# controller.net
KiCad netlist of a schematic drawn in EAGLE
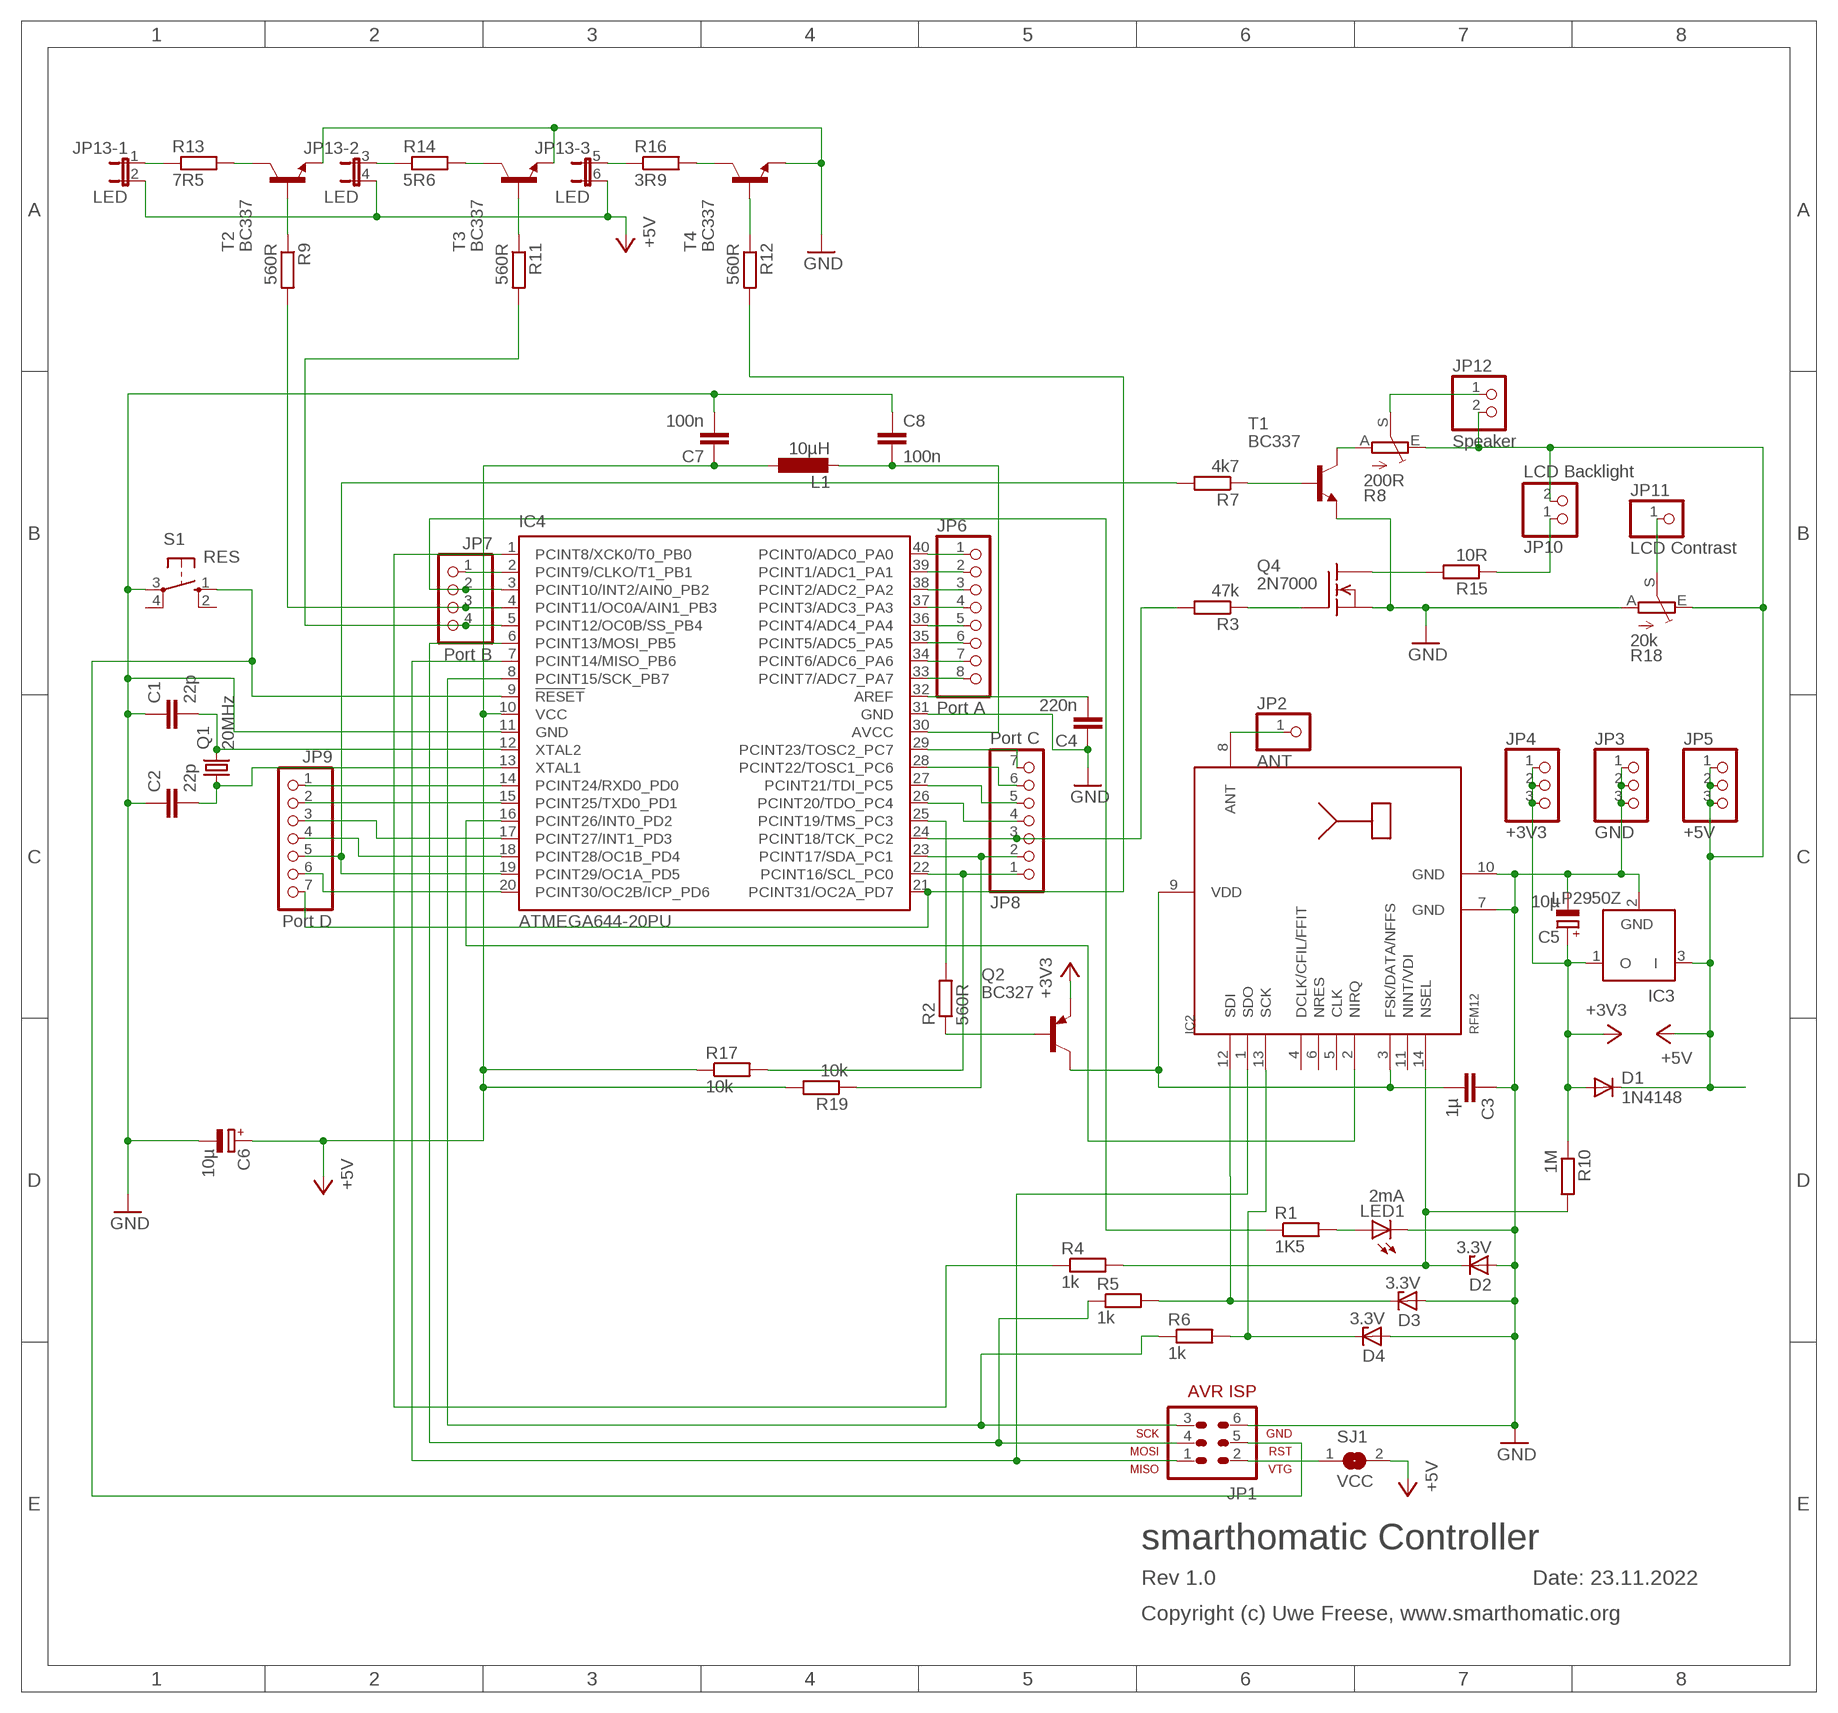
[diagram p0: schematic, sheet 1]

(export (version "E")
  (design (tool "Eeschema 10.0.6"))
  (components
    (comp (ref "C1")
      (value "22p")
      (footprint "eagle-import:C025-024X044")
      (libsource (lib "eagle-import") (part "C-EU025-024X044"))
    )
    (comp (ref "C2")
      (value "22p")
      (footprint "eagle-import:C025-024X044")
      (libsource (lib "eagle-import") (part "C-EU025-024X044"))
    )
    (comp (ref "C3")
      (value "1µ")
      (footprint "eagle-import:C025-030X050")
      (libsource (lib "eagle-import") (part "C-EU025-030X050"))
    )
    (comp (ref "C4")
      (value "220n")
      (footprint "eagle-import:C025-030X050")
      (libsource (lib "eagle-import") (part "C-EU025-030X050"))
    )
    (comp (ref "C5")
      (value "10µ")
      (footprint "eagle-import:E1,8-4")
      (libsource (lib "eagle-import") (part "CPOL-EUE1.8-4"))
    )
    (comp (ref "C6")
      (value "10µ")
      (footprint "eagle-import:E1,8-4")
      (libsource (lib "eagle-import") (part "CPOL-EUE1.8-4"))
    )
    (comp (ref "C7")
      (value "100n")
      (footprint "eagle-import:C050-024X044")
      (libsource (lib "eagle-import") (part "C-EU050-024X044"))
    )
    (comp (ref "C8")
      (value "100n")
      (footprint "eagle-import:C050-024X044")
      (libsource (lib "eagle-import") (part "C-EU050-024X044"))
    )
    (comp (ref "D1")
      (value "1N4148")
      (footprint "eagle-import:DO35-7")
      (libsource (lib "eagle-import") (part "1N4148DO35-7"))
    )
    (comp (ref "D2")
      (value "3.3V")
      (footprint "eagle-import:ZDIO-5")
      (libsource (lib "eagle-import") (part "ZENER-DIODEZD-5"))
    )
    (comp (ref "D3")
      (value "3.3V")
      (footprint "eagle-import:ZDIO-5")
      (libsource (lib "eagle-import") (part "ZENER-DIODEZD-5"))
    )
    (comp (ref "D4")
      (value "3.3V")
      (footprint "eagle-import:ZDIO-5")
      (libsource (lib "eagle-import") (part "ZENER-DIODEZD-5"))
    )
    (comp (ref "IC2")
      (value "RFM12")
      (footprint "eagle-import:RFM")
      (libsource (lib "eagle-import") (part "RFM12"))
    )
    (comp (ref "IC3")
      (value "LP2950Z")
      (footprint "eagle-import:TO92")
      (libsource (lib "eagle-import") (part "LP2950Z"))
    )
    (comp (ref "IC4")
      (value "ATMEGA644-20PU")
      (footprint "eagle-import:DIL40")
      (libsource (lib "eagle-import") (part "ATMEGA644-PU20"))
    )
    (comp (ref "JP1")
      (value "AVR-ISP-6")
      (footprint "eagle-import:AVR-ISP-6")
      (libsource (lib "eagle-import") (part "AVR-ISP-6"))
    )
    (comp (ref "JP2")
      (value "ANT")
      (footprint "eagle-import:1X01")
      (libsource (lib "eagle-import") (part "PINHD-1X1"))
    )
    (comp (ref "JP3")
      (value "GND")
      (footprint "eagle-import:1X03")
      (libsource (lib "eagle-import") (part "PINHD-1X3"))
    )
    (comp (ref "JP4")
      (value "+3V3")
      (footprint "eagle-import:1X03")
      (libsource (lib "eagle-import") (part "PINHD-1X3"))
    )
    (comp (ref "JP5")
      (value "+5V")
      (footprint "eagle-import:1X03")
      (libsource (lib "eagle-import") (part "PINHD-1X3"))
    )
    (comp (ref "JP6")
      (value "Port A")
      (footprint "eagle-import:1X08")
      (libsource (lib "eagle-import") (part "PINHD-1X8"))
    )
    (comp (ref "JP7")
      (value "Port B")
      (footprint "eagle-import:1X04")
      (libsource (lib "eagle-import") (part "PINHD-1X4"))
    )
    (comp (ref "JP8")
      (value "Port C")
      (footprint "eagle-import:1X07")
      (libsource (lib "eagle-import") (part "PINHD-1X7"))
    )
    (comp (ref "JP9")
      (value "Port D")
      (footprint "eagle-import:1X07")
      (libsource (lib "eagle-import") (part "PINHD-1X7"))
    )
    (comp (ref "JP10")
      (value "LCD Backlight")
      (footprint "eagle-import:1X02")
      (libsource (lib "eagle-import") (part "PINHD-1X2"))
    )
    (comp (ref "JP11")
      (value "LCD Contrast")
      (footprint "eagle-import:1X01")
      (libsource (lib "eagle-import") (part "PINHD-1X1"))
    )
    (comp (ref "JP12")
      (value "Speaker")
      (footprint "eagle-import:1X02")
      (libsource (lib "eagle-import") (part "PINHD-1X2"))
    )
    (comp (ref "JP13")
      (value "LED")
      (footprint "eagle-import:JP3Q")
      (libsource (lib "eagle-import") (part "JP3QE"))
    )
    (comp (ref "L1")
      (value "10µH")
      (footprint "eagle-import:0207_10")
      (libsource (lib "eagle-import") (part "L-EU0207/10"))
    )
    (comp (ref "LED1")
      (value "2mA")
      (footprint "eagle-import:LED3MM")
      (libsource (lib "eagle-import") (part "LED3MM"))
    )
    (comp (ref "Q1")
      (value "20MHz")
      (footprint "eagle-import:HC49_S")
      (libsource (lib "eagle-import") (part "CRYSTALHC49S"))
    )
    (comp (ref "Q2")
      (value "BC327")
      (footprint "eagle-import:TO92")
      (libsource (lib "eagle-import") (part "BC327"))
    )
    (comp (ref "Q4")
      (value "2N7000")
      (footprint "eagle-import:TO-92")
      (libsource (lib "eagle-import") (part "TN0602N3"))
    )
    (comp (ref "R1")
      (value "1K5")
      (footprint "eagle-import:0207_7")
      (libsource (lib "eagle-import") (part "R-EU_0207/7"))
    )
    (comp (ref "R2")
      (value "560R")
      (footprint "eagle-import:0207_7")
      (libsource (lib "eagle-import") (part "R-EU_0207/7"))
    )
    (comp (ref "R3")
      (value "47k")
      (footprint "eagle-import:0207_7")
      (libsource (lib "eagle-import") (part "R-EU_0207/7"))
    )
    (comp (ref "R4")
      (value "1k")
      (footprint "eagle-import:0207_7")
      (libsource (lib "eagle-import") (part "R-EU_0207/7"))
    )
    (comp (ref "R5")
      (value "1k")
      (footprint "eagle-import:0207_7")
      (libsource (lib "eagle-import") (part "R-EU_0207/7"))
    )
    (comp (ref "R6")
      (value "1k")
      (footprint "eagle-import:0207_7")
      (libsource (lib "eagle-import") (part "R-EU_0207/7"))
    )
    (comp (ref "R7")
      (value "4k7")
      (footprint "eagle-import:0207_7")
      (libsource (lib "eagle-import") (part "R-EU_0207/7"))
    )
    (comp (ref "R8")
      (value "200R")
      (footprint "eagle-import:CA9H")
      (libsource (lib "eagle-import") (part "TRIM_EU-CA9H"))
    )
    (comp (ref "R9")
      (value "560R")
      (footprint "eagle-import:0207_7")
      (libsource (lib "eagle-import") (part "R-EU_0207/7"))
    )
    (comp (ref "R10")
      (value "1M")
      (footprint "eagle-import:0207_7")
      (libsource (lib "eagle-import") (part "R-EU_0207/7"))
    )
    (comp (ref "R11")
      (value "560R")
      (footprint "eagle-import:0207_7")
      (libsource (lib "eagle-import") (part "R-EU_0207/7"))
    )
    (comp (ref "R12")
      (value "560R")
      (footprint "eagle-import:0207_7")
      (libsource (lib "eagle-import") (part "R-EU_0207/7"))
    )
    (comp (ref "R13")
      (value "7R5")
      (footprint "eagle-import:0207_7")
      (libsource (lib "eagle-import") (part "R-EU_0207/7"))
    )
    (comp (ref "R14")
      (value "5R6")
      (footprint "eagle-import:0207_7")
      (libsource (lib "eagle-import") (part "R-EU_0207/7"))
    )
    (comp (ref "R15")
      (value "10R")
      (footprint "eagle-import:0207_7")
      (libsource (lib "eagle-import") (part "R-EU_0207/7"))
    )
    (comp (ref "R16")
      (value "3R9")
      (footprint "eagle-import:0207_7")
      (libsource (lib "eagle-import") (part "R-EU_0207/7"))
    )
    (comp (ref "R17")
      (value "10k")
      (footprint "eagle-import:0207_7")
      (libsource (lib "eagle-import") (part "R-EU_0207/7"))
    )
    (comp (ref "R18")
      (value "20k")
      (footprint "eagle-import:CA9H")
      (libsource (lib "eagle-import") (part "TRIM_EU-CA9H"))
    )
    (comp (ref "R19")
      (value "10k")
      (footprint "eagle-import:0207_7")
      (libsource (lib "eagle-import") (part "R-EU_0207/7"))
    )
    (comp (ref "S1")
      (value "RES")
      (footprint "eagle-import:B3F-10XX")
      (fields (field (name "MPN") "B3F-1000"))
      (libsource (lib "eagle-import") (part "10-XX"))
    )
    (comp (ref "SJ1")
      (value "VCC")
      (footprint "eagle-import:SJ")
      (libsource (lib "eagle-import") (part "SJ"))
    )
    (comp (ref "T1")
      (value "BC337")
      (footprint "eagle-import:TO92")
      (libsource (lib "eagle-import") (part "BC337"))
    )
    (comp (ref "T2")
      (value "BC337")
      (footprint "eagle-import:TO92")
      (libsource (lib "eagle-import") (part "BC337"))
    )
    (comp (ref "T3")
      (value "BC337")
      (footprint "eagle-import:TO92")
      (libsource (lib "eagle-import") (part "BC337"))
    )
    (comp (ref "T4")
      (value "BC337")
      (footprint "eagle-import:TO92")
      (libsource (lib "eagle-import") (part "BC337"))
    )
  )
  (nets
    (net (code "1") (name "+3V3") (class "Default")
      (node (ref "C5") (pin "+") (pinfunction "+_+") (pintype "passive"))
      (node (ref "D1") (pin "A") (pinfunction "A_A") (pintype "passive"))
      (node (ref "IC3") (pin "1") (pinfunction "O_1") (pintype "input"))
      (node (ref "JP4") (pin "1") (pinfunction "1_1") (pintype "passive"))
      (node (ref "JP4") (pin "2") (pinfunction "2_2") (pintype "passive"))
      (node (ref "JP4") (pin "3") (pinfunction "3_3") (pintype "passive"))
      (node (ref "Q2") (pin "1") (pinfunction "E_1") (pintype "passive"))
      (node (ref "R10") (pin "1") (pinfunction "1_1") (pintype "passive"))
    )
    (net (code "2") (name "+5V") (class "Default")
      (node (ref "C6") (pin "+") (pinfunction "+_+") (pintype "passive"))
      (node (ref "C7") (pin "1") (pinfunction "1_1") (pintype "passive"))
      (node (ref "D1") (pin "C") (pinfunction "C_C") (pintype "passive"))
      (node (ref "IC3") (pin "3") (pinfunction "I_3") (pintype "input"))
      (node (ref "IC4") (pin "10") (pinfunction "VCC_10") (pintype "power_in"))
      (node (ref "JP10") (pin "2") (pinfunction "2_2") (pintype "passive"))
      (node (ref "JP12") (pin "2") (pinfunction "2_2") (pintype "passive"))
      (node (ref "JP13") (pin "2") (pinfunction "2_2") (pintype "passive"))
      (node (ref "JP13") (pin "4") (pinfunction "2_4") (pintype "passive"))
      (node (ref "JP13") (pin "6") (pinfunction "2_6") (pintype "passive"))
      (node (ref "JP5") (pin "1") (pinfunction "1_1") (pintype "passive"))
      (node (ref "JP5") (pin "2") (pinfunction "2_2") (pintype "passive"))
      (node (ref "JP5") (pin "3") (pinfunction "3_3") (pintype "passive"))
      (node (ref "L1") (pin "1") (pinfunction "1_1") (pintype "passive"))
      (node (ref "R17") (pin "1") (pinfunction "1_1") (pintype "passive"))
      (node (ref "R18") (pin "E") (pinfunction "E_E") (pintype "passive"))
      (node (ref "R19") (pin "2") (pinfunction "2_2") (pintype "passive"))
      (node (ref "R8") (pin "E") (pinfunction "E_E") (pintype "passive"))
      (node (ref "SJ1") (pin "2") (pinfunction "2_2") (pintype "passive"))
    )
    (net (code "3") (name "GND") (class "Default")
      (node (ref "C1") (pin "1") (pinfunction "1_1") (pintype "passive"))
      (node (ref "C2") (pin "1") (pinfunction "1_1") (pintype "passive"))
      (node (ref "C3") (pin "1") (pinfunction "1_1") (pintype "passive"))
      (node (ref "C4") (pin "1") (pinfunction "1_1") (pintype "passive"))
      (node (ref "C5") (pin "-") (pinfunction "-_-") (pintype "passive"))
      (node (ref "C6") (pin "-") (pinfunction "-_-") (pintype "passive"))
      (node (ref "C7") (pin "2") (pinfunction "2_2") (pintype "passive"))
      (node (ref "C8") (pin "1") (pinfunction "1_1") (pintype "passive"))
      (node (ref "D2") (pin "A") (pinfunction "A_A") (pintype "passive"))
      (node (ref "D3") (pin "A") (pinfunction "A_A") (pintype "passive"))
      (node (ref "D4") (pin "A") (pinfunction "A_A") (pintype "passive"))
      (node (ref "IC2") (pin "10") (pinfunction "GND_10") (pintype "power_in"))
      (node (ref "IC2") (pin "7") (pinfunction "GND_7") (pintype "power_in"))
      (node (ref "IC3") (pin "2") (pinfunction "GND_2") (pintype "power_in"))
      (node (ref "IC4") (pin "11") (pinfunction "GND_11") (pintype "power_in"))
      (node (ref "IC4") (pin "31") (pinfunction "GND_31") (pintype "power_in"))
      (node (ref "JP1") (pin "6") (pinfunction "6_6") (pintype "passive"))
      (node (ref "JP3") (pin "1") (pinfunction "1_1") (pintype "passive"))
      (node (ref "JP3") (pin "2") (pinfunction "2_2") (pintype "passive"))
      (node (ref "JP3") (pin "3") (pinfunction "3_3") (pintype "passive"))
      (node (ref "LED1") (pin "K") (pinfunction "C_K") (pintype "passive"))
      (node (ref "Q4") (pin "1") (pinfunction "S_1") (pintype "passive"))
      (node (ref "R18") (pin "A") (pinfunction "A_A") (pintype "passive"))
      (node (ref "S1") (pin "3") (pinfunction "P_3") (pintype "passive"))
      (node (ref "T1") (pin "1") (pinfunction "E_1") (pintype "passive"))
      (node (ref "T2") (pin "1") (pinfunction "E_1") (pintype "passive"))
      (node (ref "T3") (pin "1") (pinfunction "E_1") (pintype "passive"))
      (node (ref "T4") (pin "1") (pinfunction "E_1") (pintype "passive"))
    )
    (net (code "4") (name "Net-(IC2-ANT)") (class "Default")
      (node (ref "IC2") (pin "8") (pinfunction "ANT_8") (pintype "output"))
      (node (ref "JP2") (pin "1") (pinfunction "1_1") (pintype "passive"))
    )
    (net (code "5") (name "Net-(IC2-FSK{slash}DATA{slash}NFFS)") (class "Default")
      (node (ref "C3") (pin "2") (pinfunction "2_2") (pintype "passive"))
      (node (ref "IC2") (pin "3") (pinfunction "FSK/DATA/NFFS_3") (pintype "bidirectional"))
      (node (ref "IC2") (pin "9") (pinfunction "VDD_9") (pintype "power_in"))
      (node (ref "Q2") (pin "3") (pinfunction "C_3") (pintype "passive"))
    )
    (net (code "6") (name "Net-(IC2-NIRQ)") (class "Default")
      (node (ref "IC2") (pin "2") (pinfunction "NIRQ_2") (pintype "bidirectional"))
      (node (ref "IC4") (pin "16") (pinfunction "PCINT26/INT0_PD2_16") (pintype "bidirectional"))
    )
    (net (code "7") (name "Net-(IC2-NSEL)") (class "Default")
      (node (ref "D2") (pin "C") (pinfunction "C_C") (pintype "passive"))
      (node (ref "IC2") (pin "14") (pinfunction "NSEL_14") (pintype "bidirectional"))
      (node (ref "R10") (pin "2") (pinfunction "2_2") (pintype "passive"))
      (node (ref "R4") (pin "2") (pinfunction "2_2") (pintype "passive"))
    )
    (net (code "8") (name "Net-(IC2-SCK)") (class "Default")
      (node (ref "D4") (pin "C") (pinfunction "C_C") (pintype "passive"))
      (node (ref "IC2") (pin "13") (pinfunction "SCK_13") (pintype "bidirectional"))
      (node (ref "R6") (pin "2") (pinfunction "2_2") (pintype "passive"))
    )
    (net (code "9") (name "Net-(IC2-SDI)") (class "Default")
      (node (ref "D3") (pin "C") (pinfunction "C_C") (pintype "passive"))
      (node (ref "IC2") (pin "12") (pinfunction "SDI_12") (pintype "bidirectional"))
      (node (ref "R5") (pin "2") (pinfunction "2_2") (pintype "passive"))
    )
    (net (code "10") (name "Net-(IC2-SDO)") (class "Default")
      (node (ref "IC2") (pin "1") (pinfunction "SDO_1") (pintype "bidirectional"))
      (node (ref "IC4") (pin "7") (pinfunction "PCINT14/MISO_PB6_7") (pintype "bidirectional"))
      (node (ref "JP1") (pin "1") (pinfunction "1_1") (pintype "passive"))
    )
    (net (code "11") (name "Net-(IC4-AREF)") (class "Default")
      (node (ref "C4") (pin "2") (pinfunction "2_2") (pintype "passive"))
      (node (ref "IC4") (pin "32") (pinfunction "AREF_32") (pintype "passive"))
    )
    (net (code "12") (name "Net-(IC4-AVCC)") (class "Default")
      (node (ref "C8") (pin "2") (pinfunction "2_2") (pintype "passive"))
      (node (ref "IC4") (pin "30") (pinfunction "AVCC_30") (pintype "power_in"))
      (node (ref "L1") (pin "2") (pinfunction "2_2") (pintype "passive"))
    )
    (net (code "13") (name "Net-(IC4-PCINT0{slash}ADC0_PA0)") (class "Default")
      (node (ref "IC4") (pin "40") (pinfunction "PCINT0/ADC0_PA0_40") (pintype "bidirectional"))
      (node (ref "JP6") (pin "1") (pinfunction "1_1") (pintype "passive"))
    )
    (net (code "14") (name "Net-(IC4-PCINT1{slash}ADC1_PA1)") (class "Default")
      (node (ref "IC4") (pin "39") (pinfunction "PCINT1/ADC1_PA1_39") (pintype "bidirectional"))
      (node (ref "JP6") (pin "2") (pinfunction "2_2") (pintype "passive"))
    )
    (net (code "15") (name "Net-(IC4-PCINT2{slash}ADC2_PA2)") (class "Default")
      (node (ref "IC4") (pin "38") (pinfunction "PCINT2/ADC2_PA2_38") (pintype "bidirectional"))
      (node (ref "JP6") (pin "3") (pinfunction "3_3") (pintype "passive"))
    )
    (net (code "16") (name "Net-(IC4-PCINT3{slash}ADC3_PA3)") (class "Default")
      (node (ref "IC4") (pin "37") (pinfunction "PCINT3/ADC3_PA3_37") (pintype "bidirectional"))
      (node (ref "JP6") (pin "4") (pinfunction "4_4") (pintype "passive"))
    )
    (net (code "17") (name "Net-(IC4-PCINT4{slash}ADC4_PA4)") (class "Default")
      (node (ref "IC4") (pin "36") (pinfunction "PCINT4/ADC4_PA4_36") (pintype "bidirectional"))
      (node (ref "JP6") (pin "5") (pinfunction "5_5") (pintype "passive"))
    )
    (net (code "18") (name "Net-(IC4-PCINT5{slash}ADC5_PA5)") (class "Default")
      (node (ref "IC4") (pin "35") (pinfunction "PCINT5/ADC5_PA5_35") (pintype "bidirectional"))
      (node (ref "JP6") (pin "6") (pinfunction "6_6") (pintype "passive"))
    )
    (net (code "19") (name "Net-(IC4-PCINT6{slash}ADC6_PA6)") (class "Default")
      (node (ref "IC4") (pin "34") (pinfunction "PCINT6/ADC6_PA6_34") (pintype "bidirectional"))
      (node (ref "JP6") (pin "7") (pinfunction "7_7") (pintype "passive"))
    )
    (net (code "20") (name "Net-(IC4-PCINT7{slash}ADC7_PA7)") (class "Default")
      (node (ref "IC4") (pin "33") (pinfunction "PCINT7/ADC7_PA7_33") (pintype "bidirectional"))
      (node (ref "JP6") (pin "8") (pinfunction "8_8") (pintype "passive"))
    )
    (net (code "21") (name "Net-(IC4-PCINT8{slash}XCK0{slash}T0_PB0)") (class "Default")
      (node (ref "IC4") (pin "1") (pinfunction "PCINT8/XCK0/T0_PB0_1") (pintype "bidirectional"))
      (node (ref "R4") (pin "1") (pinfunction "1_1") (pintype "passive"))
    )
    (net (code "22") (name "Net-(IC4-PCINT9{slash}CLKO{slash}T1_PB1)") (class "Default")
      (node (ref "IC4") (pin "2") (pinfunction "PCINT9/CLKO/T1_PB1_2") (pintype "bidirectional"))
      (node (ref "JP7") (pin "1") (pinfunction "1_1") (pintype "passive"))
    )
    (net (code "23") (name "Net-(IC4-PCINT10{slash}INT2{slash}AIN0_PB2)") (class "Default")
      (node (ref "IC4") (pin "3") (pinfunction "PCINT10/INT2/AIN0_PB2_3") (pintype "bidirectional"))
      (node (ref "JP7") (pin "2") (pinfunction "2_2") (pintype "passive"))
      (node (ref "R1") (pin "1") (pinfunction "1_1") (pintype "passive"))
    )
    (net (code "24") (name "Net-(IC4-PCINT11{slash}OC0A{slash}AIN1_PB3)") (class "Default")
      (node (ref "IC4") (pin "4") (pinfunction "PCINT11/OC0A/AIN1_PB3_4") (pintype "bidirectional"))
      (node (ref "JP7") (pin "3") (pinfunction "3_3") (pintype "passive"))
      (node (ref "R9") (pin "2") (pinfunction "2_2") (pintype "passive"))
    )
    (net (code "25") (name "Net-(IC4-PCINT12{slash}OC0B{slash}SS_PB4)") (class "Default")
      (node (ref "IC4") (pin "5") (pinfunction "PCINT12/OC0B/SS_PB4_5") (pintype "bidirectional"))
      (node (ref "JP7") (pin "4") (pinfunction "4_4") (pintype "passive"))
      (node (ref "R11") (pin "2") (pinfunction "2_2") (pintype "passive"))
    )
    (net (code "26") (name "Net-(IC4-PCINT13{slash}MOSI_PB5)") (class "Default")
      (node (ref "IC4") (pin "6") (pinfunction "PCINT13/MOSI_PB5_6") (pintype "bidirectional"))
      (node (ref "JP1") (pin "4") (pinfunction "4_4") (pintype "passive"))
      (node (ref "R5") (pin "1") (pinfunction "1_1") (pintype "passive"))
    )
    (net (code "27") (name "Net-(IC4-PCINT15{slash}SCK_PB7)") (class "Default")
      (node (ref "IC4") (pin "8") (pinfunction "PCINT15/SCK_PB7_8") (pintype "bidirectional"))
      (node (ref "JP1") (pin "3") (pinfunction "3_3") (pintype "passive"))
      (node (ref "R6") (pin "1") (pinfunction "1_1") (pintype "passive"))
    )
    (net (code "28") (name "Net-(IC4-PCINT16{slash}SCL_PC0)") (class "Default")
      (node (ref "IC4") (pin "22") (pinfunction "PCINT16/SCL_PC0_22") (pintype "bidirectional"))
      (node (ref "JP8") (pin "1") (pinfunction "1_1") (pintype "passive"))
      (node (ref "R17") (pin "2") (pinfunction "2_2") (pintype "passive"))
    )
    (net (code "29") (name "Net-(IC4-PCINT17{slash}SDA_PC1)") (class "Default")
      (node (ref "IC4") (pin "23") (pinfunction "PCINT17/SDA_PC1_23") (pintype "bidirectional"))
      (node (ref "JP8") (pin "2") (pinfunction "2_2") (pintype "passive"))
      (node (ref "R19") (pin "1") (pinfunction "1_1") (pintype "passive"))
    )
    (net (code "30") (name "Net-(IC4-PCINT18{slash}TCK_PC2)") (class "Default")
      (node (ref "IC4") (pin "24") (pinfunction "PCINT18/TCK_PC2_24") (pintype "bidirectional"))
      (node (ref "JP8") (pin "3") (pinfunction "3_3") (pintype "passive"))
      (node (ref "R3") (pin "2") (pinfunction "2_2") (pintype "passive"))
    )
    (net (code "31") (name "Net-(IC4-PCINT19{slash}TMS_PC3)") (class "Default")
      (node (ref "IC4") (pin "25") (pinfunction "PCINT19/TMS_PC3_25") (pintype "bidirectional"))
      (node (ref "R2") (pin "2") (pinfunction "2_2") (pintype "passive"))
    )
    (net (code "32") (name "Net-(IC4-PCINT20{slash}TDO_PC4)") (class "Default")
      (node (ref "IC4") (pin "26") (pinfunction "PCINT20/TDO_PC4_26") (pintype "bidirectional"))
      (node (ref "JP8") (pin "4") (pinfunction "4_4") (pintype "passive"))
    )
    (net (code "33") (name "Net-(IC4-PCINT21{slash}TDI_PC5)") (class "Default")
      (node (ref "IC4") (pin "27") (pinfunction "PCINT21/TDI_PC5_27") (pintype "bidirectional"))
      (node (ref "JP8") (pin "5") (pinfunction "5_5") (pintype "passive"))
    )
    (net (code "34") (name "Net-(IC4-PCINT22{slash}TOSC1_PC6)") (class "Default")
      (node (ref "IC4") (pin "28") (pinfunction "PCINT22/TOSC1_PC6_28") (pintype "bidirectional"))
      (node (ref "JP8") (pin "6") (pinfunction "6_6") (pintype "passive"))
    )
    (net (code "35") (name "Net-(IC4-PCINT23{slash}TOSC2_PC7)") (class "Default")
      (node (ref "IC4") (pin "29") (pinfunction "PCINT23/TOSC2_PC7_29") (pintype "bidirectional"))
      (node (ref "JP8") (pin "7") (pinfunction "7_7") (pintype "passive"))
    )
    (net (code "36") (name "Net-(IC4-PCINT24{slash}RXD0_PD0)") (class "Default")
      (node (ref "IC4") (pin "14") (pinfunction "PCINT24/RXD0_PD0_14") (pintype "bidirectional"))
      (node (ref "JP9") (pin "1") (pinfunction "1_1") (pintype "passive"))
    )
    (net (code "37") (name "Net-(IC4-PCINT25{slash}TXD0_PD1)") (class "Default")
      (node (ref "IC4") (pin "15") (pinfunction "PCINT25/TXD0_PD1_15") (pintype "bidirectional"))
      (node (ref "JP9") (pin "2") (pinfunction "2_2") (pintype "passive"))
    )
    (net (code "38") (name "Net-(IC4-PCINT27{slash}INT1_PD3)") (class "Default")
      (node (ref "IC4") (pin "17") (pinfunction "PCINT27/INT1_PD3_17") (pintype "bidirectional"))
      (node (ref "JP9") (pin "3") (pinfunction "3_3") (pintype "passive"))
    )
    (net (code "39") (name "Net-(IC4-PCINT28{slash}OC1B_PD4)") (class "Default")
      (node (ref "IC4") (pin "18") (pinfunction "PCINT28/OC1B_PD4_18") (pintype "bidirectional"))
      (node (ref "JP9") (pin "4") (pinfunction "4_4") (pintype "passive"))
    )
    (net (code "40") (name "Net-(IC4-PCINT29{slash}OC1A_PD5)") (class "Default")
      (node (ref "IC4") (pin "19") (pinfunction "PCINT29/OC1A_PD5_19") (pintype "bidirectional"))
      (node (ref "JP9") (pin "5") (pinfunction "5_5") (pintype "passive"))
      (node (ref "R7") (pin "2") (pinfunction "2_2") (pintype "passive"))
    )
    (net (code "41") (name "Net-(IC4-PCINT30{slash}OC2B{slash}ICP_PD6)") (class "Default")
      (node (ref "IC4") (pin "20") (pinfunction "PCINT30/OC2B/ICP_PD6_20") (pintype "bidirectional"))
      (node (ref "JP9") (pin "6") (pinfunction "6_6") (pintype "passive"))
    )
    (net (code "42") (name "Net-(IC4-PCINT31{slash}OC2A_PD7)") (class "Default")
      (node (ref "IC4") (pin "21") (pinfunction "PCINT31/OC2A_PD7_21") (pintype "bidirectional"))
      (node (ref "JP9") (pin "7") (pinfunction "7_7") (pintype "passive"))
      (node (ref "R12") (pin "2") (pinfunction "2_2") (pintype "passive"))
    )
    (net (code "43") (name "Net-(IC4-XTAL1)") (class "Default")
      (node (ref "C2") (pin "2") (pinfunction "2_2") (pintype "passive"))
      (node (ref "IC4") (pin "13") (pinfunction "XTAL1_13") (pintype "input"))
      (node (ref "Q1") (pin "1") (pinfunction "1_1") (pintype "passive"))
    )
    (net (code "44") (name "Net-(IC4-XTAL2)") (class "Default")
      (node (ref "C1") (pin "2") (pinfunction "2_2") (pintype "passive"))
      (node (ref "IC4") (pin "12") (pinfunction "XTAL2_12") (pintype "output"))
      (node (ref "Q1") (pin "2") (pinfunction "2_2") (pintype "passive"))
    )
    (net (code "45") (name "Net-(IC4-~{RESET})") (class "Default")
      (node (ref "IC4") (pin "9") (pinfunction "~{RESET}_9") (pintype "input"))
      (node (ref "JP1") (pin "5") (pinfunction "5_5") (pintype "passive"))
      (node (ref "S1") (pin "1") (pinfunction "S_1") (pintype "passive"))
    )
    (net (code "46") (name "Net-(JP1-Pad2)") (class "Default")
      (node (ref "JP1") (pin "2") (pinfunction "2_2") (pintype "passive"))
      (node (ref "SJ1") (pin "1") (pinfunction "1_1") (pintype "passive"))
    )
    (net (code "47") (name "Net-(JP10-Pad1)") (class "Default")
      (node (ref "JP10") (pin "1") (pinfunction "1_1") (pintype "passive"))
      (node (ref "R15") (pin "1") (pinfunction "1_1") (pintype "passive"))
    )
    (net (code "48") (name "Net-(JP11-Pad1)") (class "Default")
      (node (ref "JP11") (pin "1") (pinfunction "1_1") (pintype "passive"))
      (node (ref "R18") (pin "S") (pinfunction "S_S") (pintype "passive"))
    )
    (net (code "49") (name "Net-(JP12-Pad1)") (class "Default")
      (node (ref "JP12") (pin "1") (pinfunction "1_1") (pintype "passive"))
      (node (ref "R8") (pin "S") (pinfunction "S_S") (pintype "passive"))
    )
    (net (code "50") (name "Net-(JP13-Pad1)") (class "Default")
      (node (ref "JP13") (pin "1") (pinfunction "1_1") (pintype "passive"))
      (node (ref "R13") (pin "1") (pinfunction "1_1") (pintype "passive"))
    )
    (net (code "51") (name "Net-(JP13B-1)") (class "Default")
      (node (ref "JP13") (pin "3") (pinfunction "1_3") (pintype "passive"))
      (node (ref "R14") (pin "1") (pinfunction "1_1") (pintype "passive"))
    )
    (net (code "52") (name "Net-(JP13C-1)") (class "Default")
      (node (ref "JP13") (pin "5") (pinfunction "1_5") (pintype "passive"))
      (node (ref "R16") (pin "1") (pinfunction "1_1") (pintype "passive"))
    )
    (net (code "53") (name "Net-(LED1-PadA)") (class "Default")
      (node (ref "LED1") (pin "A") (pinfunction "A_A") (pintype "passive"))
      (node (ref "R1") (pin "2") (pinfunction "2_2") (pintype "passive"))
    )
    (net (code "54") (name "Net-(Q2-B)") (class "Default")
      (node (ref "Q2") (pin "2") (pinfunction "B_2") (pintype "passive"))
      (node (ref "R2") (pin "1") (pinfunction "1_1") (pintype "passive"))
    )
    (net (code "55") (name "Net-(Q4-D)") (class "Default")
      (node (ref "Q4") (pin "3") (pinfunction "D_3") (pintype "passive"))
      (node (ref "R15") (pin "2") (pinfunction "2_2") (pintype "passive"))
    )
    (net (code "56") (name "Net-(Q4-G)") (class "Default")
      (node (ref "Q4") (pin "2") (pinfunction "G_2") (pintype "passive"))
      (node (ref "R3") (pin "1") (pinfunction "1_1") (pintype "passive"))
    )
    (net (code "57") (name "Net-(T1-B)") (class "Default")
      (node (ref "R7") (pin "1") (pinfunction "1_1") (pintype "passive"))
      (node (ref "T1") (pin "2") (pinfunction "B_2") (pintype "passive"))
    )
    (net (code "58") (name "Net-(T1-C)") (class "Default")
      (node (ref "R8") (pin "A") (pinfunction "A_A") (pintype "passive"))
      (node (ref "T1") (pin "3") (pinfunction "C_3") (pintype "passive"))
    )
    (net (code "59") (name "Net-(T2-B)") (class "Default")
      (node (ref "R9") (pin "1") (pinfunction "1_1") (pintype "passive"))
      (node (ref "T2") (pin "2") (pinfunction "B_2") (pintype "passive"))
    )
    (net (code "60") (name "Net-(T2-C)") (class "Default")
      (node (ref "R13") (pin "2") (pinfunction "2_2") (pintype "passive"))
      (node (ref "T2") (pin "3") (pinfunction "C_3") (pintype "passive"))
    )
    (net (code "61") (name "Net-(T3-B)") (class "Default")
      (node (ref "R11") (pin "1") (pinfunction "1_1") (pintype "passive"))
      (node (ref "T3") (pin "2") (pinfunction "B_2") (pintype "passive"))
    )
    (net (code "62") (name "Net-(T3-C)") (class "Default")
      (node (ref "R14") (pin "2") (pinfunction "2_2") (pintype "passive"))
      (node (ref "T3") (pin "3") (pinfunction "C_3") (pintype "passive"))
    )
    (net (code "63") (name "Net-(T4-B)") (class "Default")
      (node (ref "R12") (pin "1") (pinfunction "1_1") (pintype "passive"))
      (node (ref "T4") (pin "2") (pinfunction "B_2") (pintype "passive"))
    )
    (net (code "64") (name "Net-(T4-C)") (class "Default")
      (node (ref "R16") (pin "2") (pinfunction "2_2") (pintype "passive"))
      (node (ref "T4") (pin "3") (pinfunction "C_3") (pintype "passive"))
    )
    (net (code "65") (name "unconnected-(IC2-CLK-Pad5)") (class "Default")
      (node (ref "IC2") (pin "5") (pinfunction "CLK_5") (pintype "bidirectional"))
    )
    (net (code "66") (name "unconnected-(IC2-DCLK{slash}CFIL{slash}FFIT-Pad4)") (class "Default")
      (node (ref "IC2") (pin "4") (pinfunction "DCLK/CFIL/FFIT_4") (pintype "bidirectional"))
    )
    (net (code "67") (name "unconnected-(IC2-NINT{slash}VDI-Pad11)") (class "Default")
      (node (ref "IC2") (pin "11") (pinfunction "NINT/VDI_11") (pintype "bidirectional"))
    )
    (net (code "68") (name "unconnected-(IC2-NRES-Pad6)") (class "Default")
      (node (ref "IC2") (pin "6") (pinfunction "NRES_6") (pintype "bidirectional"))
    )
    (net (code "69") (name "unconnected-(S1-P1-Pad4)") (class "Default")
      (node (ref "S1") (pin "4") (pinfunction "P1_4") (pintype "passive"))
    )
    (net (code "70") (name "unconnected-(S1-S1-Pad2)") (class "Default")
      (node (ref "S1") (pin "2") (pinfunction "S1_2") (pintype "passive"))
    )
  )
)
